# CW308T_SI4010_main.net
KiCad netlist of a schematic drawn in Altium Designer
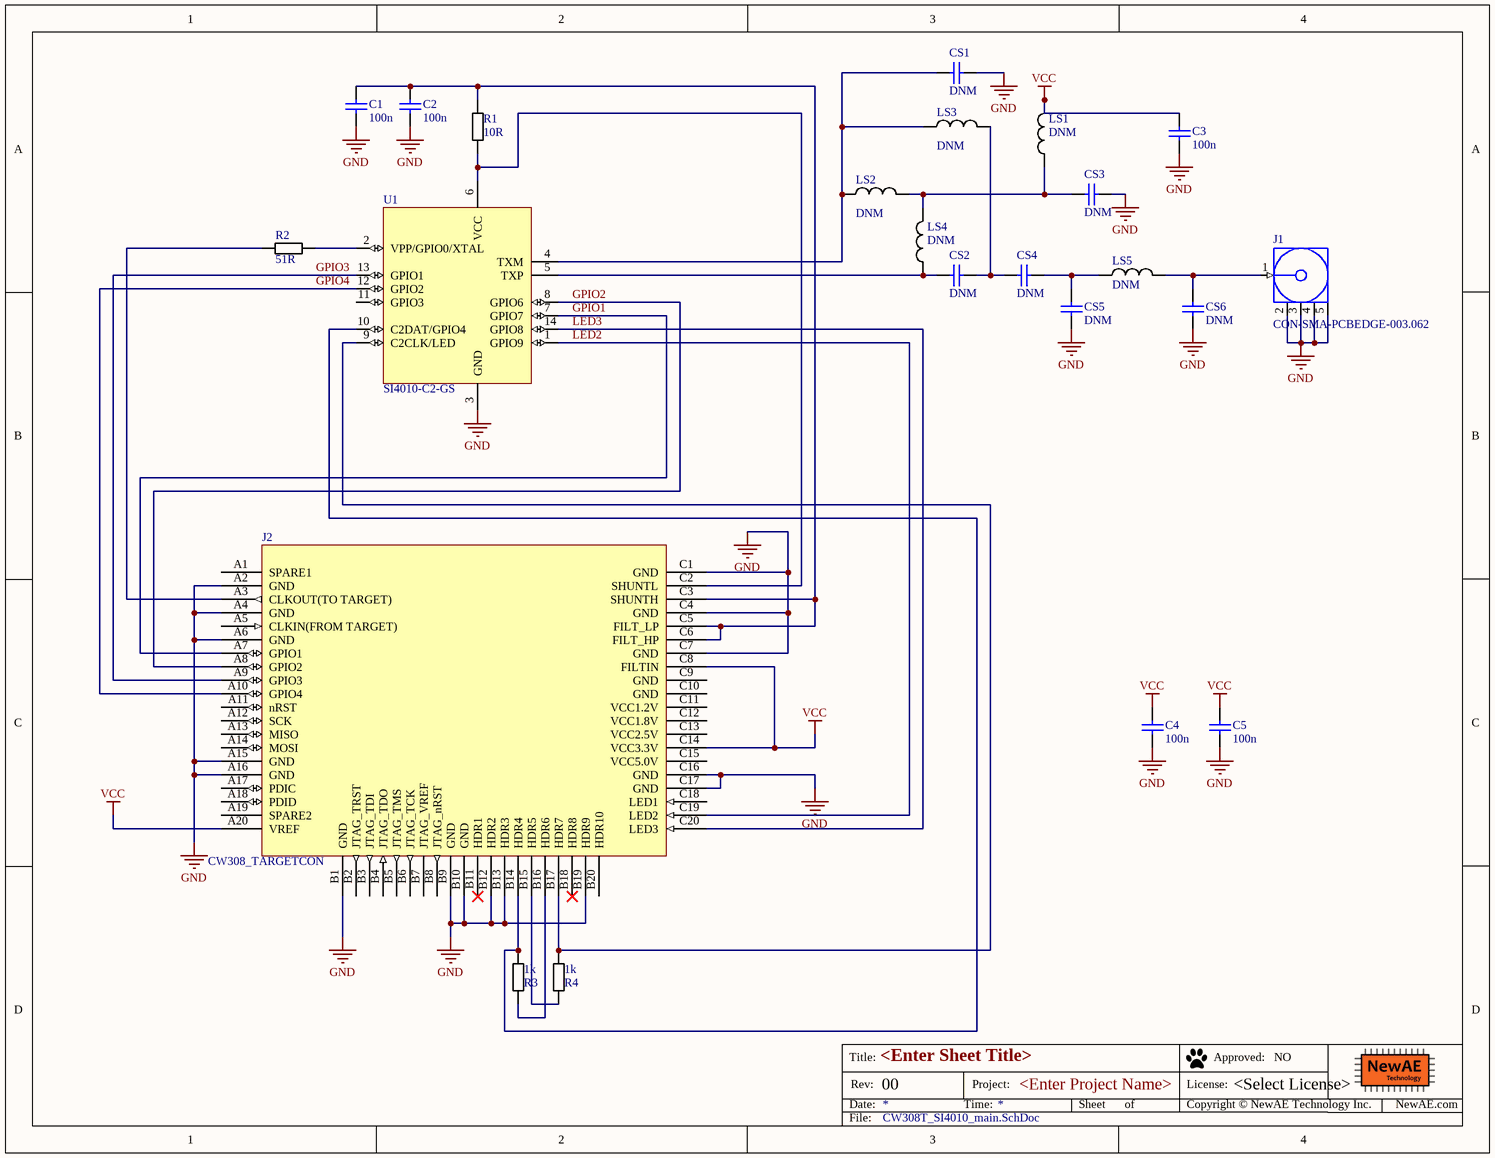
[diagram p0: CW308T_SI4010_main.SchDoc]

(export (version "E")
  (design (tool "Eeschema 10.0.6"))
  (components
    (comp (ref "C1")
      (value "100n")
      (footprint "CAPC0603_M")
      (description "100n, 0603")
      (fields (field (name "PART NUMBER") "CCHIP-100n-0603"))
      (libsource (lib "NewAE_AltiumLib") (part "CAP"))
    )
    (comp (ref "C2")
      (value "100n")
      (footprint "CAPC0603_M")
      (description "100n, 0603")
      (fields (field (name "PART NUMBER") "CCHIP-100n-0603"))
      (libsource (lib "NewAE_AltiumLib") (part "CAP"))
    )
    (comp (ref "C3")
      (value "100n")
      (footprint "CAPC0603_M")
      (description "100n, 0603")
      (fields (field (name "PART NUMBER") "CCHIP-100n-0603"))
      (libsource (lib "NewAE_AltiumLib") (part "CAP"))
    )
    (comp (ref "C4")
      (value "100n")
      (footprint "CAPC0603_M")
      (description "100n, 0603")
      (fields (field (name "PART NUMBER") "CCHIP-100n-0603"))
      (libsource (lib "NewAE_AltiumLib") (part "CAP"))
    )
    (comp (ref "C5")
      (value "100n")
      (footprint "CAPC0603_M")
      (description "100n, 0603")
      (fields (field (name "PART NUMBER") "CCHIP-100n-0603"))
      (libsource (lib "NewAE_AltiumLib") (part "CAP"))
    )
    (comp (ref "CS1")
      (value "DNM")
      (footprint "CAPC0402_M")
      (description "DNM, 0402")
      (fields (field (name "PART NUMBER") "CCHIP-DNM-0402"))
      (libsource (lib "NewAE_AltiumLib") (part "CAP"))
    )
    (comp (ref "CS2")
      (value "DNM")
      (footprint "CAPC0402_M")
      (description "DNM, 0402")
      (fields (field (name "PART NUMBER") "CCHIP-DNM-0402"))
      (libsource (lib "NewAE_AltiumLib") (part "CAP"))
    )
    (comp (ref "CS3")
      (value "DNM")
      (footprint "CAPC0402_M")
      (description "DNM, 0402")
      (fields (field (name "PART NUMBER") "CCHIP-DNM-0402"))
      (libsource (lib "NewAE_AltiumLib") (part "CAP"))
    )
    (comp (ref "CS4")
      (value "DNM")
      (footprint "CAPC0402_M")
      (description "DNM, 0402")
      (fields (field (name "PART NUMBER") "CCHIP-DNM-0402"))
      (libsource (lib "NewAE_AltiumLib") (part "CAP"))
    )
    (comp (ref "CS5")
      (value "DNM")
      (footprint "CAPC0402_M")
      (description "DNM, 0402")
      (fields (field (name "PART NUMBER") "CCHIP-DNM-0402"))
      (libsource (lib "NewAE_AltiumLib") (part "CAP"))
    )
    (comp (ref "CS6")
      (value "DNM")
      (footprint "CAPC0402_M")
      (description "DNM, 0402")
      (fields (field (name "PART NUMBER") "CCHIP-DNM-0402"))
      (libsource (lib "NewAE_AltiumLib") (part "CAP"))
    )
    (comp (ref "J1")
      (value "CON-SMA-PCBEDGE-003.062")
      (footprint "CON-SMAM-PCB-EDGE062")
      (description "SMA Female Edge Mount Connector for 0.062\" Thick Board")
      (libsource (lib "NewAE_AltiumLib") (part "CON-SMA-PCBEDGE-003.062"))
    )
    (comp (ref "J2")
      (value "CW308_TARGETCON")
      (footprint "CW308_TBOARD_CONN")
      (description "CW308 \"Standard\" Target Board Connector")
      (fields (field (name "PART NUMBER") "CW308_TBOARD"))
      (libsource (lib "NewAE_AltiumLib") (part "CW308_TBOARD"))
    )
    (comp (ref "LS1")
      (value "DNM")
      (footprint "RESC1005X40N")
      (description "DNM, 0402")
      (fields (field (name "PART NUMBER") "LCHIP-DNM-0402"))
      (libsource (lib "NewAE_AltiumLib") (part "IND"))
    )
    (comp (ref "LS2")
      (value "DNM")
      (footprint "RESC1005X40N")
      (description "DNM, 0402")
      (fields (field (name "PART NUMBER") "LCHIP-DNM-0402"))
      (libsource (lib "NewAE_AltiumLib") (part "IND"))
    )
    (comp (ref "LS3")
      (value "DNM")
      (footprint "RESC1005X40N")
      (description "DNM, 0402")
      (fields (field (name "PART NUMBER") "LCHIP-DNM-0402"))
      (libsource (lib "NewAE_AltiumLib") (part "IND"))
    )
    (comp (ref "LS4")
      (value "DNM")
      (footprint "RESC1005X40N")
      (description "DNM, 0402")
      (fields (field (name "PART NUMBER") "LCHIP-DNM-0402"))
      (libsource (lib "NewAE_AltiumLib") (part "IND"))
    )
    (comp (ref "LS5")
      (value "DNM")
      (footprint "RESC1005X40N")
      (description "DNM, 0402")
      (fields (field (name "PART NUMBER") "LCHIP-DNM-0402"))
      (libsource (lib "NewAE_AltiumLib") (part "IND"))
    )
    (comp (ref "R1")
      (value "10R")
      (footprint "RESC1608X55N")
      (description "10R res, 0603, 1%, 1/10W")
      (fields (field (name "PART NUMBER") "RCHIP-10R-0603") (field (name "TOLERANCE") "1%"))
      (libsource (lib "NewAE_AltiumLib") (part "RES-EU"))
    )
    (comp (ref "R2")
      (value "51R")
      (footprint "RESC1608X55N")
      (description "51R res, 0603, 1%, 1/10W")
      (fields (field (name "PART NUMBER") "RCHIP-51R-0603") (field (name "TOLERANCE") "1%"))
      (libsource (lib "") (part "RES-EU_1"))
    )
    (comp (ref "R3")
      (value "1k")
      (footprint "RESC1608X55N")
      (description "1k res, 0603, 1%, 1/10W")
      (fields (field (name "PART NUMBER") "RCHIP-1K-0603") (field (name "TOLERANCE") "1%"))
      (libsource (lib "NewAE_AltiumLib") (part "RES-EU"))
    )
    (comp (ref "R4")
      (value "1k")
      (footprint "RESC1608X55N")
      (description "1k res, 0603, 1%, 1/10W")
      (fields (field (name "PART NUMBER") "RCHIP-1K-0603") (field (name "TOLERANCE") "1%"))
      (libsource (lib "NewAE_AltiumLib") (part "RES-EU"))
    )
    (comp (ref "U1")
      (value "SI4010-C2-GS")
      (footprint "SOIC127P600X175-14M")
      (description "RF Transmitter FSK, OOK 27MHz ~ 960MHz, HW-AES")
      (fields (field (name "PART NUMBER") "Si4010-GS"))
      (libsource (lib "NewAE_AltiumLib") (part "Si4010-GS"))
    )
  )
  (nets
    (net (code "1") (name "/GPIO1") (class "Default")
      (node (ref "J2") (pin "A7") (pinfunction "GPIO1_A7") (pintype "bidirectional"))
      (node (ref "U1") (pin "7") (pinfunction "GPIO7_7") (pintype "bidirectional"))
    )
    (net (code "2") (name "/GPIO2") (class "Default")
      (node (ref "J2") (pin "A8") (pinfunction "GPIO2_A8") (pintype "bidirectional"))
      (node (ref "U1") (pin "8") (pinfunction "GPIO6_8") (pintype "bidirectional"))
    )
    (net (code "3") (name "/GPIO3") (class "Default")
      (node (ref "J2") (pin "A9") (pinfunction "GPIO3_A9") (pintype "bidirectional"))
      (node (ref "U1") (pin "13") (pinfunction "GPIO1_13") (pintype "bidirectional"))
    )
    (net (code "4") (name "/GPIO4") (class "Default")
      (node (ref "J2") (pin "A10") (pinfunction "GPIO4_A10") (pintype "bidirectional"))
      (node (ref "U1") (pin "12") (pinfunction "GPIO2_12") (pintype "bidirectional"))
    )
    (net (code "5") (name "/LED2") (class "Default")
      (node (ref "J2") (pin "C19") (pinfunction "LED2_C19") (pintype "input"))
      (node (ref "U1") (pin "1") (pinfunction "GPIO9_1") (pintype "bidirectional"))
    )
    (net (code "6") (name "/LED3") (class "Default")
      (node (ref "J2") (pin "C20") (pinfunction "LED3_C20") (pintype "input"))
      (node (ref "U1") (pin "14") (pinfunction "GPIO8_14") (pintype "bidirectional"))
    )
    (net (code "7") (name "GND") (class "Default")
      (node (ref "C1") (pin "1") (pinfunction "1_1") (pintype "passive"))
      (node (ref "C2") (pin "1") (pinfunction "1_1") (pintype "passive"))
      (node (ref "C3") (pin "1") (pinfunction "1_1") (pintype "passive"))
      (node (ref "C4") (pin "1") (pinfunction "1_1") (pintype "passive"))
      (node (ref "C5") (pin "1") (pinfunction "1_1") (pintype "passive"))
      (node (ref "CS1") (pin "2") (pinfunction "2_2") (pintype "passive"))
      (node (ref "CS3") (pin "2") (pinfunction "2_2") (pintype "passive"))
      (node (ref "CS5") (pin "2") (pinfunction "2_2") (pintype "passive"))
      (node (ref "CS6") (pin "2") (pinfunction "2_2") (pintype "passive"))
      (node (ref "J1") (pin "2") (pinfunction "GND_2") (pintype "power_in"))
      (node (ref "J1") (pin "3") (pinfunction "GND_3") (pintype "power_in"))
      (node (ref "J1") (pin "4") (pinfunction "GND_4") (pintype "power_in"))
      (node (ref "J1") (pin "5") (pinfunction "GND_5") (pintype "power_in"))
      (node (ref "J2") (pin "A15") (pinfunction "GND_A15") (pintype "passive"))
      (node (ref "J2") (pin "A16") (pinfunction "GND_A16") (pintype "passive"))
      (node (ref "J2") (pin "A2") (pinfunction "GND_A2") (pintype "passive"))
      (node (ref "J2") (pin "A4") (pinfunction "GND_A4") (pintype "passive"))
      (node (ref "J2") (pin "A6") (pinfunction "GND_A6") (pintype "power_in"))
      (node (ref "J2") (pin "B1") (pinfunction "GND_B1") (pintype "passive"))
      (node (ref "J2") (pin "B10") (pinfunction "GND_B10") (pintype "passive"))
      (node (ref "J2") (pin "B12") (pinfunction "HDR2_B12") (pintype "passive"))
      (node (ref "J2") (pin "B13") (pinfunction "HDR3_B13") (pintype "passive"))
      (node (ref "J2") (pin "B19") (pinfunction "HDR9_B19") (pintype "passive"))
      (node (ref "J2") (pin "B9") (pinfunction "GND_B9") (pintype "passive"))
      (node (ref "J2") (pin "C1") (pinfunction "GND_C1") (pintype "power_in"))
      (node (ref "J2") (pin "C16") (pinfunction "GND_C16") (pintype "power_in"))
      (node (ref "J2") (pin "C17") (pinfunction "GND_C17") (pintype "power_in"))
      (node (ref "J2") (pin "C4") (pinfunction "GND_C4") (pintype "power_in"))
      (node (ref "J2") (pin "C7") (pinfunction "GND_C7") (pintype "power_in"))
      (node (ref "U1") (pin "3") (pinfunction "GND_3") (pintype "power_in"))
    )
    (net (code "8") (name "Net-(CS2-Pad2)") (class "Default")
      (node (ref "CS2") (pin "2") (pinfunction "2_2") (pintype "passive"))
      (node (ref "CS4") (pin "1") (pinfunction "1_1") (pintype "passive"))
      (node (ref "LS3") (pin "2") (pinfunction "2_2") (pintype "passive"))
    )
    (net (code "9") (name "Net-(CS3-Pad1)") (class "Default")
      (node (ref "CS3") (pin "1") (pinfunction "1_1") (pintype "passive"))
      (node (ref "LS1") (pin "1") (pinfunction "1_1") (pintype "passive"))
      (node (ref "LS2") (pin "2") (pinfunction "2_2") (pintype "passive"))
      (node (ref "LS4") (pin "2") (pinfunction "2_2") (pintype "passive"))
    )
    (net (code "10") (name "Net-(CS4-Pad2)") (class "Default")
      (node (ref "CS4") (pin "2") (pinfunction "2_2") (pintype "passive"))
      (node (ref "CS5") (pin "1") (pinfunction "1_1") (pintype "passive"))
      (node (ref "LS5") (pin "1") (pinfunction "1_1") (pintype "passive"))
    )
    (net (code "11") (name "Net-(J1-Signal)") (class "Default")
      (node (ref "CS6") (pin "1") (pinfunction "1_1") (pintype "passive"))
      (node (ref "J1") (pin "1") (pinfunction "Signal_1") (pintype "input"))
      (node (ref "LS5") (pin "2") (pinfunction "2_2") (pintype "passive"))
    )
    (net (code "12") (name "Net-(J2-CLKOUT(TO_TARGET))") (class "Default")
      (node (ref "J2") (pin "A3") (pinfunction "CLKOUT(TO_TARGET)_A3") (pintype "output"))
      (node (ref "R2") (pin "1") (pinfunction "1_1") (pintype "passive"))
    )
    (net (code "13") (name "Net-(J2-FILT_HP)") (class "Default")
      (node (ref "C1") (pin "2") (pinfunction "2_2") (pintype "passive"))
      (node (ref "C2") (pin "2") (pinfunction "2_2") (pintype "passive"))
      (node (ref "J2") (pin "C3") (pinfunction "SHUNTH_C3") (pintype "passive"))
      (node (ref "J2") (pin "C5") (pinfunction "FILT_LP_C5") (pintype "passive"))
      (node (ref "J2") (pin "C6") (pinfunction "FILT_HP_C6") (pintype "passive"))
      (node (ref "R1") (pin "1") (pinfunction "1_1") (pintype "passive"))
    )
    (net (code "14") (name "Net-(J2-HDR4)") (class "Default")
      (node (ref "J2") (pin "B14") (pinfunction "HDR4_B14") (pintype "passive"))
      (node (ref "R3") (pin "1") (pinfunction "1_1") (pintype "passive"))
      (node (ref "U1") (pin "10") (pinfunction "C2DAT/GPIO4_10") (pintype "bidirectional"))
    )
    (net (code "15") (name "Net-(J2-HDR5)") (class "Default")
      (node (ref "J2") (pin "B15") (pinfunction "HDR5_B15") (pintype "passive"))
      (node (ref "R4") (pin "2") (pinfunction "2_2") (pintype "passive"))
    )
    (net (code "16") (name "Net-(J2-HDR6)") (class "Default")
      (node (ref "J2") (pin "B16") (pinfunction "HDR6_B16") (pintype "passive"))
      (node (ref "R3") (pin "2") (pinfunction "2_2") (pintype "passive"))
    )
    (net (code "17") (name "Net-(J2-HDR7)") (class "Default")
      (node (ref "J2") (pin "B17") (pinfunction "HDR7_B17") (pintype "passive"))
      (node (ref "R4") (pin "1") (pinfunction "1_1") (pintype "passive"))
      (node (ref "U1") (pin "9") (pinfunction "C2CLK/LED_9") (pintype "bidirectional"))
    )
    (net (code "18") (name "Net-(J2-SHUNTL)") (class "Default")
      (node (ref "J2") (pin "C2") (pinfunction "SHUNTL_C2") (pintype "passive"))
      (node (ref "R1") (pin "2") (pinfunction "2_2") (pintype "passive"))
      (node (ref "U1") (pin "6") (pinfunction "VCC_6") (pintype "power_in"))
    )
    (net (code "19") (name "Net-(U1-TXM)") (class "Default")
      (node (ref "CS1") (pin "1") (pinfunction "1_1") (pintype "passive"))
      (node (ref "LS2") (pin "1") (pinfunction "1_1") (pintype "passive"))
      (node (ref "LS3") (pin "1") (pinfunction "1_1") (pintype "passive"))
      (node (ref "U1") (pin "4") (pinfunction "TXM_4") (pintype "passive"))
    )
    (net (code "20") (name "Net-(U1-TXP)") (class "Default")
      (node (ref "CS2") (pin "1") (pinfunction "1_1") (pintype "passive"))
      (node (ref "LS4") (pin "1") (pinfunction "1_1") (pintype "passive"))
      (node (ref "U1") (pin "5") (pinfunction "TXP_5") (pintype "passive"))
    )
    (net (code "21") (name "Net-(U1-VPP{slash}GPIO0{slash}XTAL)") (class "Default")
      (node (ref "R2") (pin "2") (pinfunction "2_2") (pintype "passive"))
      (node (ref "U1") (pin "2") (pinfunction "VPP/GPIO0/XTAL_2") (pintype "bidirectional"))
    )
    (net (code "22") (name "VCC") (class "Default")
      (node (ref "C3") (pin "2") (pinfunction "2_2") (pintype "passive"))
      (node (ref "C4") (pin "2") (pinfunction "2_2") (pintype "passive"))
      (node (ref "C5") (pin "2") (pinfunction "2_2") (pintype "passive"))
      (node (ref "J2") (pin "A20") (pinfunction "VREF_A20") (pintype "tri_state"))
      (node (ref "J2") (pin "C14") (pinfunction "VCC3.3V_C14") (pintype "power_in"))
      (node (ref "J2") (pin "C8") (pinfunction "FILTIN_C8") (pintype "passive"))
      (node (ref "LS1") (pin "2") (pinfunction "2_2") (pintype "passive"))
    )
    (net (code "23") (name "unconnected-(J2-CLKIN(FROM_TARGET)-PadA5)") (class "Default")
      (node (ref "J2") (pin "A5") (pinfunction "CLKIN(FROM_TARGET)_A5") (pintype "input"))
    )
    (net (code "24") (name "unconnected-(J2-GND-PadC9)") (class "Default")
      (node (ref "J2") (pin "C9") (pinfunction "GND_C9") (pintype "power_in"))
    )
    (net (code "25") (name "unconnected-(J2-GND-PadC10)") (class "Default")
      (node (ref "J2") (pin "C10") (pinfunction "GND_C10") (pintype "power_in"))
    )
    (net (code "26") (name "unconnected-(J2-HDR1-PadB11)") (class "Default")
      (node (ref "J2") (pin "B11") (pinfunction "HDR1_B11") (pintype "passive+no_connect"))
    )
    (net (code "27") (name "unconnected-(J2-HDR8-PadB18)") (class "Default")
      (node (ref "J2") (pin "B18") (pinfunction "HDR8_B18") (pintype "passive+no_connect"))
    )
    (net (code "28") (name "unconnected-(J2-HDR10-PadB20)") (class "Default")
      (node (ref "J2") (pin "B20") (pinfunction "HDR10_B20") (pintype "passive"))
    )
    (net (code "29") (name "unconnected-(J2-JTAG_TCK-PadB6)") (class "Default")
      (node (ref "J2") (pin "B6") (pinfunction "JTAG_TCK_B6") (pintype "output"))
    )
    (net (code "30") (name "unconnected-(J2-JTAG_TDI-PadB3)") (class "Default")
      (node (ref "J2") (pin "B3") (pinfunction "JTAG_TDI_B3") (pintype "output"))
    )
    (net (code "31") (name "unconnected-(J2-JTAG_TDO-PadB4)") (class "Default")
      (node (ref "J2") (pin "B4") (pinfunction "JTAG_TDO_B4") (pintype "input"))
    )
    (net (code "32") (name "unconnected-(J2-JTAG_TMS-PadB5)") (class "Default")
      (node (ref "J2") (pin "B5") (pinfunction "JTAG_TMS_B5") (pintype "output"))
    )
    (net (code "33") (name "unconnected-(J2-JTAG_TRST-PadB2)") (class "Default")
      (node (ref "J2") (pin "B2") (pinfunction "JTAG_TRST_B2") (pintype "output"))
    )
    (net (code "34") (name "unconnected-(J2-JTAG_VREF-PadB7)") (class "Default")
      (node (ref "J2") (pin "B7") (pinfunction "JTAG_VREF_B7") (pintype "tri_state"))
    )
    (net (code "35") (name "unconnected-(J2-JTAG_nRST-PadB8)") (class "Default")
      (node (ref "J2") (pin "B8") (pinfunction "JTAG_nRST_B8") (pintype "output"))
    )
    (net (code "36") (name "unconnected-(J2-LED1-PadC18)") (class "Default")
      (node (ref "J2") (pin "C18") (pinfunction "LED1_C18") (pintype "input"))
    )
    (net (code "37") (name "unconnected-(J2-MISO-PadA13)") (class "Default")
      (node (ref "J2") (pin "A13") (pinfunction "MISO_A13") (pintype "bidirectional"))
    )
    (net (code "38") (name "unconnected-(J2-MOSI-PadA14)") (class "Default")
      (node (ref "J2") (pin "A14") (pinfunction "MOSI_A14") (pintype "bidirectional"))
    )
    (net (code "39") (name "unconnected-(J2-PDIC-PadA17)") (class "Default")
      (node (ref "J2") (pin "A17") (pinfunction "PDIC_A17") (pintype "bidirectional"))
    )
    (net (code "40") (name "unconnected-(J2-PDID-PadA18)") (class "Default")
      (node (ref "J2") (pin "A18") (pinfunction "PDID_A18") (pintype "bidirectional"))
    )
    (net (code "41") (name "unconnected-(J2-SCK-PadA12)") (class "Default")
      (node (ref "J2") (pin "A12") (pinfunction "SCK_A12") (pintype "bidirectional"))
    )
    (net (code "42") (name "unconnected-(J2-SPARE1-PadA1)") (class "Default")
      (node (ref "J2") (pin "A1") (pinfunction "SPARE1_A1") (pintype "passive"))
    )
    (net (code "43") (name "unconnected-(J2-SPARE2-PadA19)") (class "Default")
      (node (ref "J2") (pin "A19") (pinfunction "SPARE2_A19") (pintype "passive"))
    )
    (net (code "44") (name "unconnected-(J2-VCC1.2V-PadC11)") (class "Default")
      (node (ref "J2") (pin "C11") (pinfunction "VCC1.2V_C11") (pintype "power_in"))
    )
    (net (code "45") (name "unconnected-(J2-VCC1.8V-PadC12)") (class "Default")
      (node (ref "J2") (pin "C12") (pinfunction "VCC1.8V_C12") (pintype "power_in"))
    )
    (net (code "46") (name "unconnected-(J2-VCC2.5V-PadC13)") (class "Default")
      (node (ref "J2") (pin "C13") (pinfunction "VCC2.5V_C13") (pintype "power_in"))
    )
    (net (code "47") (name "unconnected-(J2-VCC5.0V-PadC15)") (class "Default")
      (node (ref "J2") (pin "C15") (pinfunction "VCC5.0V_C15") (pintype "power_in"))
    )
    (net (code "48") (name "unconnected-(J2-nRST-PadA11)") (class "Default")
      (node (ref "J2") (pin "A11") (pinfunction "nRST_A11") (pintype "bidirectional"))
    )
    (net (code "49") (name "unconnected-(U1-GPIO3-Pad11)") (class "Default")
      (node (ref "U1") (pin "11") (pinfunction "GPIO3_11") (pintype "bidirectional"))
    )
  )
)
